# Teensylu-1_0.net
KiCad netlist of a schematic drawn in EAGLE
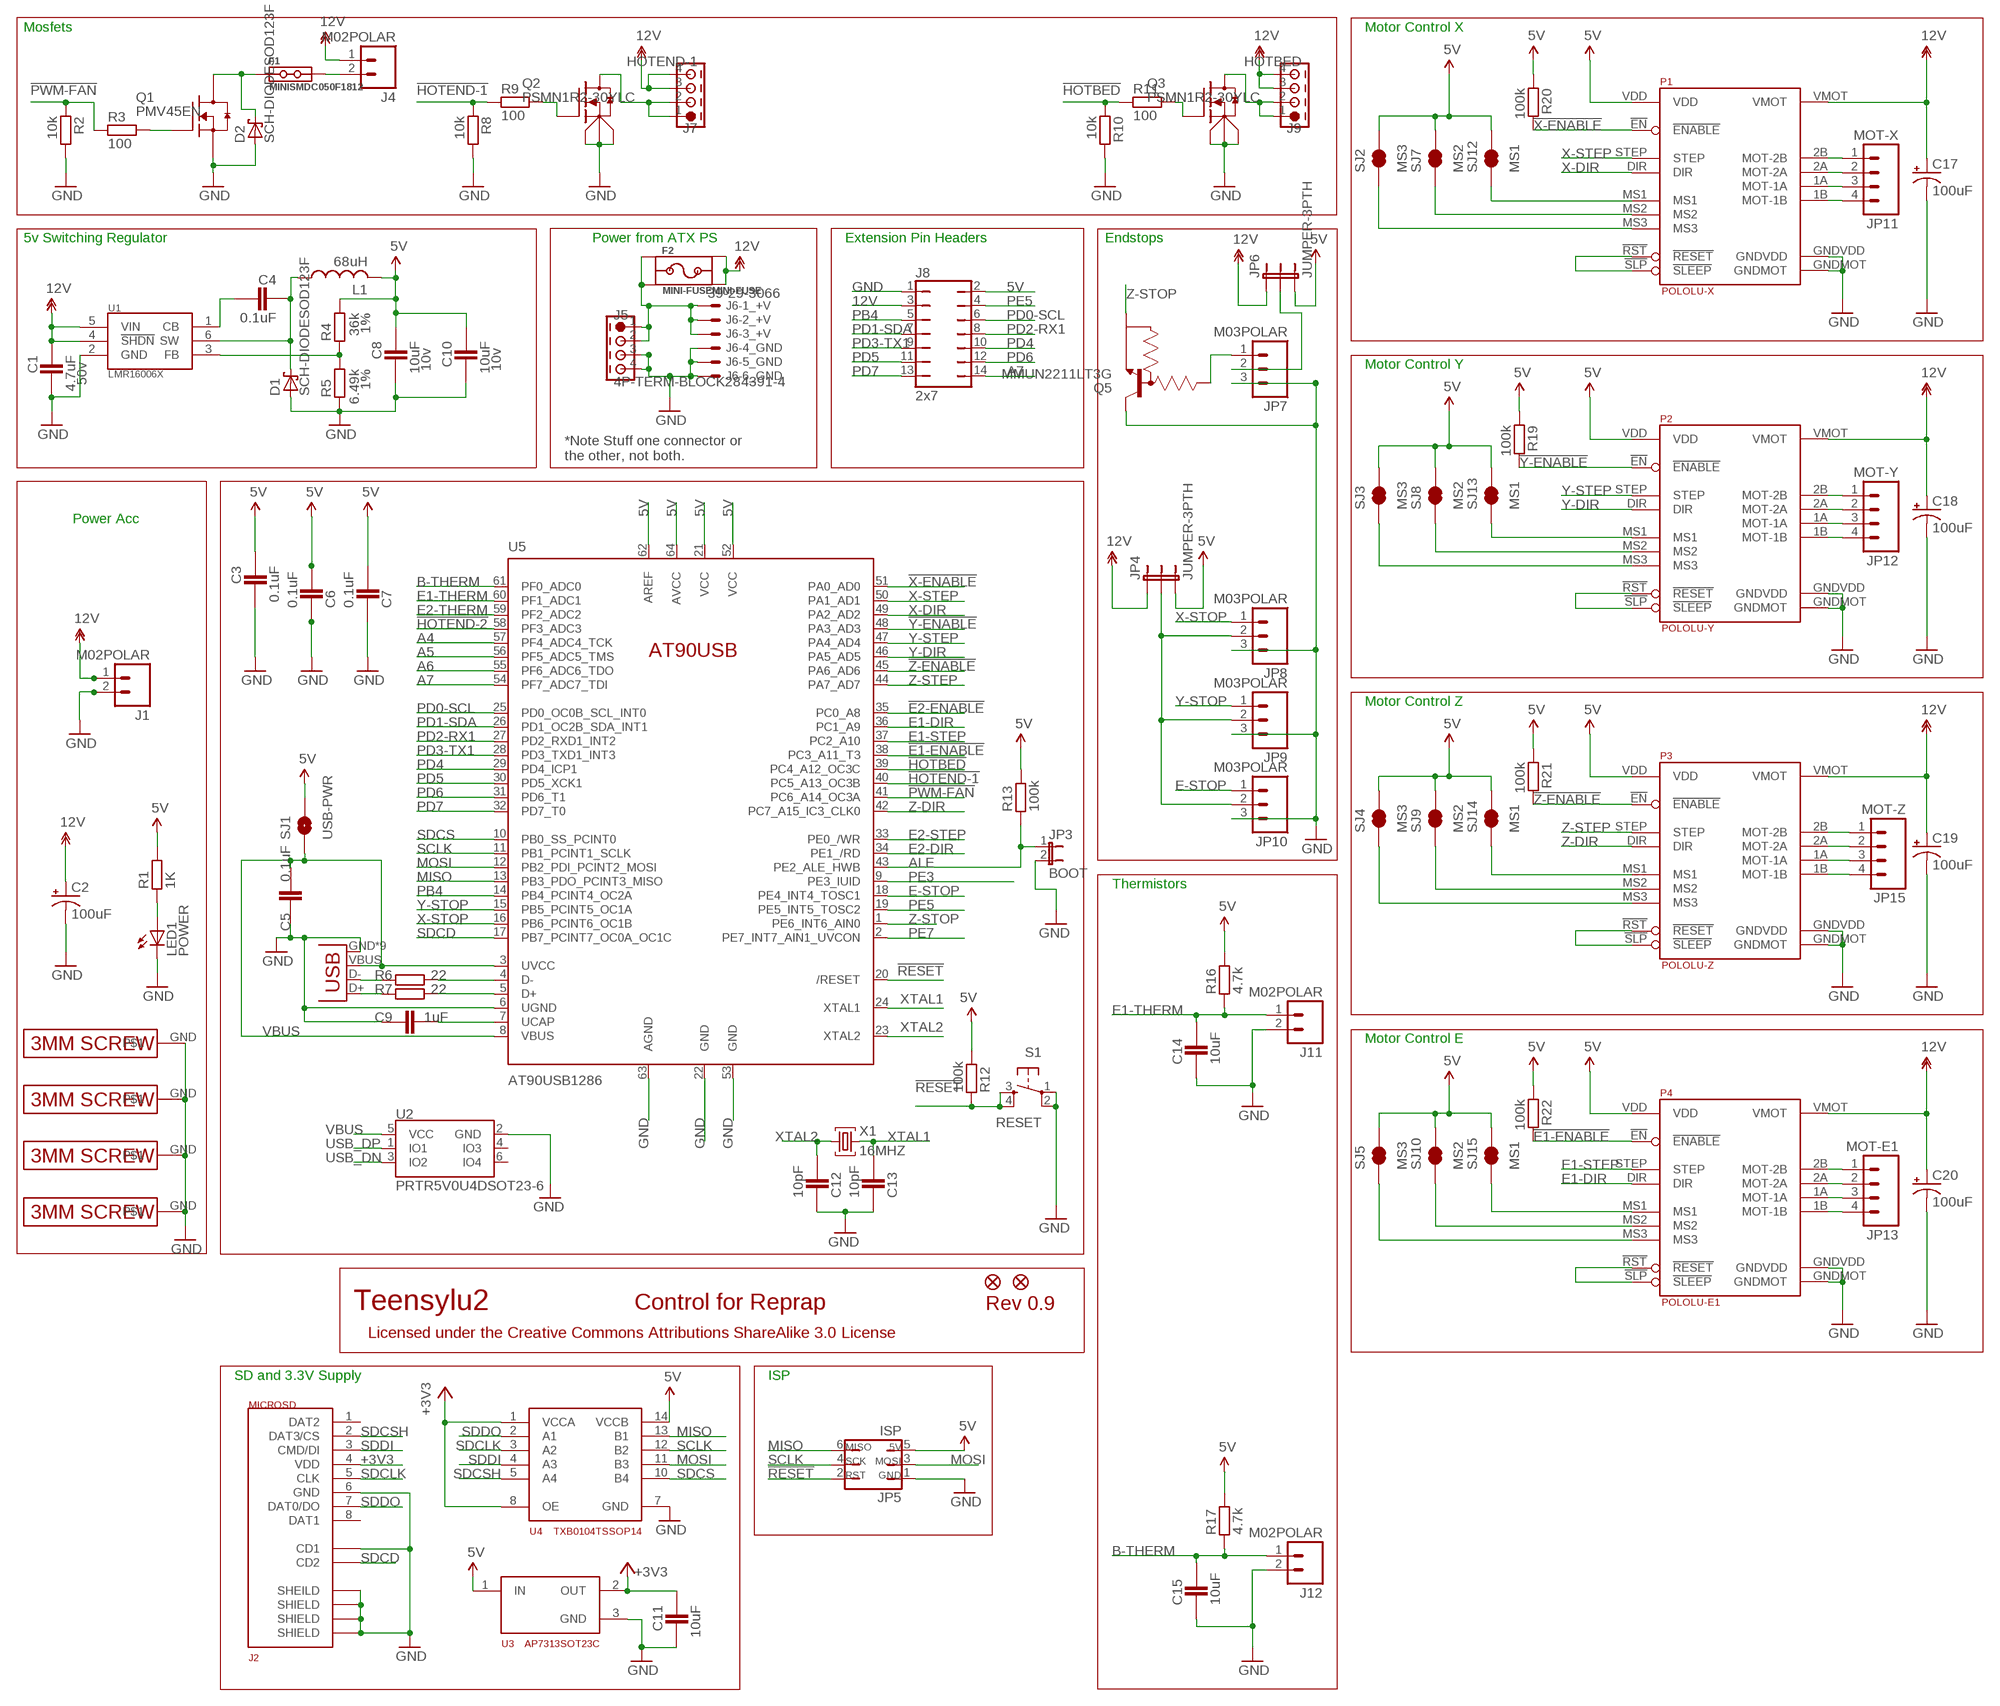
[diagram p0: schematic, sheet 1]

(export (version "E")
  (design (tool "Eeschema 10.0.6"))
  (components
    (comp (ref "C1")
      (value "4.7uF")
      (footprint "eagle-import:CAPC3215X168N")
      (fields
        (field (name "MANUFACTURER") "Yaiyo Yuden")
        (field (name "MANUFACTURER_PART_NUMBER") "UMK316AB7475KL-T")
        (field (name "TOLERANCE") "10%")
        (field (name "VDC") "50v")
      )
      (libsource (lib "eagle-import") (part "CAPACITOR_1206"))
    )
    (comp (ref "C2")
      (value "100uF")
      (footprint "eagle-import:PANASONIC_D")
      (fields
        (field (name "MANUFACTURER") "Panasonic")
        (field (name "MANUFACTURER_PART_NUMBER") "EEE-FTH101XAP")
        (field (name "TOLERANCE") "20%")
      )
      (libsource (lib "eagle-import") (part "CPOL-USD"))
    )
    (comp (ref "C3")
      (value "0.1uF")
      (footprint "eagle-import:CAPC1608X92N")
      (fields
        (field (name "MANUFACTURER") "Murata")
        (field (name "MANUFACTURER_PART_NUMBER") "GRM188R71C104KA01D")
        (field (name "TOLERANCE") "10%")
      )
      (libsource (lib "eagle-import") (part "CAPACITOR_0603"))
    )
    (comp (ref "C4")
      (value "0.1uF")
      (footprint "eagle-import:CAPC1608X92N")
      (fields
        (field (name "MANUFACTURER") "Samsung")
        (field (name "MANUFACTURER_PART_NUMBER") "CL10B104KB8NNNC")
        (field (name "TOLERANCE") "10%")
      )
      (libsource (lib "eagle-import") (part "CAPACITOR_0603"))
    )
    (comp (ref "C5")
      (value "0.1uF")
      (footprint "eagle-import:CAPC1608X92N")
      (fields
        (field (name "MANUFACTURER") "Murata")
        (field (name "MANUFACTURER_PART_NUMBER") "GRM188R71C104KA01D")
        (field (name "TOLERANCE") "10%")
      )
      (libsource (lib "eagle-import") (part "CAPACITOR_0603"))
    )
    (comp (ref "C6")
      (value "0.1uF")
      (footprint "eagle-import:CAPC1608X92N")
      (fields
        (field (name "MANUFACTURER") "Murata")
        (field (name "MANUFACTURER_PART_NUMBER") "GRM188R71C104KA01D")
        (field (name "TOLERANCE") "10%")
      )
      (libsource (lib "eagle-import") (part "CAPACITOR_0603"))
    )
    (comp (ref "C7")
      (value "0.1uF")
      (footprint "eagle-import:CAPC1608X92N")
      (fields
        (field (name "MANUFACTURER") "Murata")
        (field (name "MANUFACTURER_PART_NUMBER") "GRM188R71C104KA01D")
        (field (name "TOLERANCE") "10%")
      )
      (libsource (lib "eagle-import") (part "CAPACITOR_0603"))
    )
    (comp (ref "C8")
      (value "10uF")
      (footprint "eagle-import:CAPC2012X145AN")
      (fields
        (field (name "MANUFACTURER") "Murata")
        (field (name "MANUFACTURER_PART_NUMBER") "GRM21BR71A106KE51L")
        (field (name "TOLERANCE") "10%")
        (field (name "VDC") "10v")
      )
      (libsource (lib "eagle-import") (part "CAPACITOR_0805"))
    )
    (comp (ref "C9")
      (value "1uF")
      (footprint "eagle-import:CAPC1608X92N")
      (fields
        (field (name "MANUFACTURER") "Samsung")
        (field (name "MANUFACTURER_PART_NUMBER") "CL10A105MO8NNNC")
        (field (name "TOLERANCE") "20%")
      )
      (libsource (lib "eagle-import") (part "CAPACITOR_0603"))
    )
    (comp (ref "C10")
      (value "10uF")
      (footprint "eagle-import:CAPC2012X145AN")
      (fields
        (field (name "MANUFACTURER") "Murata")
        (field (name "MANUFACTURER_PART_NUMBER") "GRM21BR71A106KE51L")
        (field (name "TOLERANCE") "10%")
        (field (name "VDC") "10v")
      )
      (libsource (lib "eagle-import") (part "CAPACITOR_0805"))
    )
    (comp (ref "C11")
      (value "10uF")
      (footprint "eagle-import:CAPC1608X92N")
      (fields
        (field (name "MANUFACTURER") "Murata")
        (field (name "MANUFACTURER_PART_NUMBER") "GRM188R61C106MA73D")
        (field (name "TOLERANCE") "20%")
      )
      (libsource (lib "eagle-import") (part "CAPACITOR_0603"))
    )
    (comp (ref "C12")
      (value "10pF")
      (footprint "eagle-import:CAPC1608X92N")
      (fields
        (field (name "MANUFACTURER") "Samsung")
        (field (name "MANUFACTURER_PART_NUMBER") "CL10C100JB8NCNC")
        (field (name "TOLERANCE") "5%")
      )
      (libsource (lib "eagle-import") (part "CAPACITOR_0603"))
    )
    (comp (ref "C13")
      (value "10pF")
      (footprint "eagle-import:CAPC1608X92N")
      (fields
        (field (name "MANUFACTURER") "Samsung")
        (field (name "MANUFACTURER_PART_NUMBER") "CL10C100JB8NCNC")
        (field (name "TOLERANCE") "5%")
      )
      (libsource (lib "eagle-import") (part "CAPACITOR_0603"))
    )
    (comp (ref "C14")
      (value "10uF")
      (footprint "eagle-import:CAPC1608X92N")
      (fields
        (field (name "MANUFACTURER") "Murata")
        (field (name "MANUFACTURER_PART_NUMBER") "GRM188R61C106MA73D")
        (field (name "TOLERANCE") "20%")
      )
      (libsource (lib "eagle-import") (part "CAPACITOR_0603"))
    )
    (comp (ref "C15")
      (value "10uF")
      (footprint "eagle-import:CAPC1608X92N")
      (fields
        (field (name "MANUFACTURER") "Murata")
        (field (name "MANUFACTURER_PART_NUMBER") "GRM188R61C106MA73D")
        (field (name "TOLERANCE") "20%")
      )
      (libsource (lib "eagle-import") (part "CAPACITOR_0603"))
    )
    (comp (ref "C17")
      (value "100uF")
      (footprint "eagle-import:PANASONIC_D")
      (fields
        (field (name "MANUFACTURER") "Panasonic")
        (field (name "MANUFACTURER_PART_NUMBER") "EEE-FTH101XAP")
        (field (name "TOLERANCE") "20%")
      )
      (libsource (lib "eagle-import") (part "CPOL-USD"))
    )
    (comp (ref "C18")
      (value "100uF")
      (footprint "eagle-import:PANASONIC_D")
      (fields
        (field (name "MANUFACTURER") "Panasonic")
        (field (name "MANUFACTURER_PART_NUMBER") "EEE-FTH101XAP")
        (field (name "TOLERANCE") "20%")
      )
      (libsource (lib "eagle-import") (part "CPOL-USD"))
    )
    (comp (ref "C19")
      (value "100uF")
      (footprint "eagle-import:PANASONIC_D")
      (fields
        (field (name "MANUFACTURER") "Panasonic")
        (field (name "MANUFACTURER_PART_NUMBER") "EEE-FTH101XAP")
        (field (name "TOLERANCE") "20%")
      )
      (libsource (lib "eagle-import") (part "CPOL-USD"))
    )
    (comp (ref "C20")
      (value "100uF")
      (footprint "eagle-import:PANASONIC_D")
      (fields
        (field (name "MANUFACTURER") "Panasonic")
        (field (name "MANUFACTURER_PART_NUMBER") "EEE-FTH101XAP")
        (field (name "TOLERANCE") "20%")
      )
      (libsource (lib "eagle-import") (part "CPOL-USD"))
    )
    (comp (ref "D1")
      (value "SCH-DIODESOD123F")
      (footprint "eagle-import:SOD123F")
      (fields
        (field (name "MANUFACTURER") "NXP Semiconductors")
        (field (name "MANUFACTURER_PART_NUMBER") "PMEG4010CEH,115")
        (field (name "CURRENT") "1A")
        (field (name "MANUFACTURER_1") "NXP Semiconductors")
        (field (name "MANUFACTURER_PART_NUMBER_1") "PMEG4010CEH,115")
        (field (name "REVERSE_VOLTAGE") "40V")
      )
      (libsource (lib "eagle-import") (part "SCH-DIODESOD123F"))
    )
    (comp (ref "D2")
      (value "SCH-DIODESOD123F")
      (footprint "eagle-import:SOD123F")
      (fields
        (field (name "MANUFACTURER") "NXP Semiconductors")
        (field (name "MANUFACTURER_PART_NUMBER") "PMEG4010CEH,115")
        (field (name "CURRENT") "1A")
        (field (name "MANUFACTURER_1") "NXP Semiconductors")
      )
      (libsource (lib "eagle-import") (part "SCH-DIODESOD123F"))
    )
    (comp (ref "F1")
      (value "MINISMDC050F1812")
      (footprint "eagle-import:MINISMDC")
      (fields
        (field (name "MANUFACTURER") "TE Connectivity")
        (field (name "MANUFACTURER_PART_NUMBER") "MINISMDC050F-2")
      )
      (libsource (lib "eagle-import") (part "MINISMDC050F1812"))
    )
    (comp (ref "F2")
      (value "MINI-FUSEMINI-FUSE")
      (footprint "eagle-import:MINI_FUSE")
      (fields (field (name "MANUFACTURER") "Keystone") (field (name "MANUFACTURER_PART_NUMBER") "3568"))
      (libsource (lib "eagle-import") (part "MINI-FUSEMINI-FUSE"))
    )
    (comp (ref "J1")
      (value "M02POLAR")
      (footprint "eagle-import:MOLEX-1X2")
      (description "CONN HEADER 2POS .100 VERT TIN")
      (fields (field (name "MANUFACTURER") "Molex") (field (name "MANUFACTURER_PART_NUMBER") "0022272021"))
      (libsource (lib "eagle-import") (part "M02POLAR"))
    )
    (comp (ref "J2")
      (value "MICROSD")
      (footprint "eagle-import:AMPHENOL-MICROSD")
      (description "CONN MICRO SD CARD PUSH-PULL R/A")
      (fields
        (field (name "MANUFACTURER") "Amphenol")
        (field (name "MANUFACTURER_PART_NUMBER") "114-00841-68")
      )
      (libsource (lib "eagle-import") (part "MICROSD"))
    )
    (comp (ref "J3")
      (value "USB-MICRO-PTH")
      (footprint "eagle-import:USB-MICROB-PTH")
      (fields (field (name "MANUFACTURER") "FCI") (field (name "MANUFACTURER_PART_NUMBER") "10118194-0001LF"))
      (libsource (lib "eagle-import") (part "USB-MICRO-PTH"))
    )
    (comp (ref "J4")
      (value "M02POLAR")
      (footprint "eagle-import:MOLEX-1X2")
      (description "CONN HEADER 2POS .100 VERT TIN")
      (fields (field (name "MANUFACTURER") "Molex") (field (name "MANUFACTURER_PART_NUMBER") "0022272021"))
      (libsource (lib "eagle-import") (part "M02POLAR"))
    )
    (comp (ref "J5")
      (value "4P-TERM-BLOCK284391-4")
      (footprint "eagle-import:284391-4")
      (fields
        (field (name "MANUFACTURER") "TE Connectivity")
        (field (name "MANUFACTURER_PART_NUMBER") "284391-4")
      )
      (libsource (lib "eagle-import") (part "4P-TERM-BLOCK284391-4"))
    )
    (comp (ref "J6")
      (value "39-29-3066")
      (footprint "eagle-import:39-29-3066")
      (fields (field (name "MANUFACTURER") "Molex") (field (name "MANUFACTURER_PART_NUMBER") "0039293066"))
      (libsource (lib "eagle-import") (part "39-29-3066"))
    )
    (comp (ref "J7")
      (value "HOTEND-1")
      (footprint "eagle-import:284391-4")
      (fields
        (field (name "MANUFACTURER") "TE Connectivity")
        (field (name "MANUFACTURER_PART_NUMBER") "284391-4")
      )
      (libsource (lib "eagle-import") (part "4P-TERM-BLOCK284391-4"))
    )
    (comp (ref "J8")
      (value "2x7")
      (footprint "eagle-import:JP7Q")
      (description "DIL VERTICAL PC TAIL PIN HEADER")
      (fields (field (name "MANUFACTURER") "Harwin") (field (name "MANUFACTURER_PART_NUMBER") "M20-9980746"))
      (libsource (lib "eagle-import") (part "JP7Q"))
    )
    (comp (ref "J9")
      (value "HOTBED")
      (footprint "eagle-import:284391-4")
      (fields
        (field (name "MANUFACTURER") "TE Connectivity")
        (field (name "MANUFACTURER_PART_NUMBER") "284391-4")
      )
      (libsource (lib "eagle-import") (part "4P-TERM-BLOCK284391-4"))
    )
    (comp (ref "J11")
      (value "M02POLAR")
      (footprint "eagle-import:MOLEX-1X2")
      (description "CONN HEADER 2POS .100 VERT TIN")
      (fields (field (name "MANUFACTURER") "Molex") (field (name "MANUFACTURER_PART_NUMBER") "0022272021"))
      (libsource (lib "eagle-import") (part "M02POLAR"))
    )
    (comp (ref "J12")
      (value "M02POLAR")
      (footprint "eagle-import:MOLEX-1X2")
      (description "CONN HEADER 2POS .100 VERT TIN")
      (fields (field (name "MANUFACTURER") "Molex") (field (name "MANUFACTURER_PART_NUMBER") "0022272021"))
      (libsource (lib "eagle-import") (part "M02POLAR"))
    )
    (comp (ref "JP1")
      (value "FIDUCIAL1X2.5")
      (footprint "eagle-import:FIDUCIAL-1X2.5")
      (libsource (lib "eagle-import") (part "FIDUCIAL1X2.5"))
    )
    (comp (ref "JP2")
      (value "FIDUCIAL1X2.5")
      (footprint "eagle-import:FIDUCIAL-1X2.5")
      (libsource (lib "eagle-import") (part "FIDUCIAL1X2.5"))
    )
    (comp (ref "JP3")
      (value "BOOT")
      (footprint "eagle-import:1X02")
      (description "SIL VERTICAL PC TAIL PIN HEADER")
      (fields (field (name "MANUFACTURER") "Harwin") (field (name "MANUFACTURER_PART_NUMBER") "M20-9990246"))
      (libsource (lib "eagle-import") (part "JUMPER-2PTH"))
    )
    (comp (ref "JP4")
      (value "JUMPER-3PTH")
      (footprint "eagle-import:1X03")
      (libsource (lib "eagle-import") (part "JUMPER-3PTH"))
    )
    (comp (ref "JP5")
      (value "ISP")
      (footprint "eagle-import:ISP")
      (libsource (lib "eagle-import") (part "PROGHEADER"))
    )
    (comp (ref "JP6")
      (value "JUMPER-3PTH")
      (footprint "eagle-import:1X03")
      (libsource (lib "eagle-import") (part "JUMPER-3PTH"))
    )
    (comp (ref "JP7")
      (value "M03POLAR")
      (footprint "eagle-import:MOLEX-1X3")
      (description "CONN HEADER 3POS .100 VERT TIN")
      (fields (field (name "MANUFACTURER") "Molex") (field (name "MANUFACTURER_PART_NUMBER") "0022272031"))
      (libsource (lib "eagle-import") (part "M03POLAR"))
    )
    (comp (ref "JP8")
      (value "M03POLAR")
      (footprint "eagle-import:MOLEX-1X3")
      (description "CONN HEADER 3POS .100 VERT TIN")
      (fields (field (name "MANUFACTURER") "Molex") (field (name "MANUFACTURER_PART_NUMBER") "0022272031"))
      (libsource (lib "eagle-import") (part "M03POLAR"))
    )
    (comp (ref "JP9")
      (value "M03POLAR")
      (footprint "eagle-import:MOLEX-1X3")
      (description "CONN HEADER 3POS .100 VERT TIN")
      (fields (field (name "MANUFACTURER") "Molex") (field (name "MANUFACTURER_PART_NUMBER") "0022272031"))
      (libsource (lib "eagle-import") (part "M03POLAR"))
    )
    (comp (ref "JP10")
      (value "M03POLAR")
      (footprint "eagle-import:MOLEX-1X3")
      (description "CONN HEADER 3POS .100 VERT TIN")
      (fields (field (name "MANUFACTURER") "Molex") (field (name "MANUFACTURER_PART_NUMBER") "0022272031"))
      (libsource (lib "eagle-import") (part "M03POLAR"))
    )
    (comp (ref "JP11")
      (value "MOT-X")
      (footprint "eagle-import:MOLEX-1X4")
      (fields (field (name "MANUFACTURER") "Molex") (field (name "MANUFACTURER_PART_NUMBER") "0022272041"))
      (libsource (lib "eagle-import") (part "M04POLAR"))
    )
    (comp (ref "JP12")
      (value "MOT-Y")
      (footprint "eagle-import:MOLEX-1X4")
      (fields (field (name "MANUFACTURER") "Molex") (field (name "MANUFACTURER_PART_NUMBER") "0022272041"))
      (libsource (lib "eagle-import") (part "M04POLAR"))
    )
    (comp (ref "JP13")
      (value "MOT-E1")
      (footprint "eagle-import:MOLEX-1X4")
      (fields (field (name "MANUFACTURER") "Molex") (field (name "MANUFACTURER_PART_NUMBER") "0022272041"))
      (libsource (lib "eagle-import") (part "M04POLAR"))
    )
    (comp (ref "JP15")
      (value "MOT-Z")
      (footprint "eagle-import:MOLEX-1X4")
      (fields (field (name "MANUFACTURER") "Molex") (field (name "MANUFACTURER_PART_NUMBER") "0022272041"))
      (libsource (lib "eagle-import") (part "M04POLAR"))
    )
    (comp (ref "L1")
      (value "68uH")
      (footprint "eagle-import:SRN6045")
      (fields
        (field (name "MANUFACTURER") "Bourns")
        (field (name "MANUFACTURER_PART_NUMBER") "SRN6045-680M")
        (field (name "MANUFACTURER_1") "Bourns")
        (field (name "MANUFACTURER_PART_NUMBER_1") "SRN6045-680M")
      )
      (libsource (lib "eagle-import") (part "INDUCTORSRN6045"))
    )
    (comp (ref "LED1")
      (value "POWER")
      (footprint "eagle-import:CHIPLED_0805")
      (fields
        (field (name "MANUFACTURER") "Kingbright")
        (field (name "MANUFACTURER_PART_NUMBER") "APT2012SGC")
      )
      (libsource (lib "eagle-import") (part "LEDCHIPLED_0805"))
    )
    (comp (ref "P1")
      (value "POLOLU-X")
      (footprint "eagle-import:POLOLU-STEPPER-PTH")
      (libsource (lib "eagle-import") (part "POLOLU-ALLEGRO"))
    )
    (comp (ref "P2")
      (value "POLOLU-Y")
      (footprint "eagle-import:POLOLU-STEPPER-PTH")
      (libsource (lib "eagle-import") (part "POLOLU-ALLEGRO"))
    )
    (comp (ref "P3")
      (value "POLOLU-Z")
      (footprint "eagle-import:POLOLU-STEPPER-PTH")
      (libsource (lib "eagle-import") (part "POLOLU-ALLEGRO"))
    )
    (comp (ref "P4")
      (value "POLOLU-E1")
      (footprint "eagle-import:POLOLU-STEPPER-PTH")
      (libsource (lib "eagle-import") (part "POLOLU-ALLEGRO"))
    )
    (comp (ref "Q1")
      (value "PMV45EN")
      (footprint "eagle-import:SOT23C")
      (fields
        (field (name "MANUFACTURER") "International Rectifier")
        (field (name "MANUFACTURER_PART_NUMBER") "IRLML2060TRPBF")
        (field (name "VOLTAGE") "60V")
      )
      (libsource (lib "eagle-import") (part "MOSFET-NCH_SOT-23"))
    )
    (comp (ref "Q2")
      (value "PSMN1R2-30YLC")
      (footprint "eagle-import:LFPACK-POWERPAK-SO8")
      (fields
        (field (name "MANUFACTURER") "NXP Semiconductors")
        (field (name "MANUFACTURER_PART_NUMBER") "PSMN1R2-30YLC,115")
        (field (name "VOLTAGE") "30V")
      )
      (libsource (lib "eagle-import") (part "PSMN1R2-30YLCPOWERPACK-S08"))
    )
    (comp (ref "Q3")
      (value "PSMN1R2-30YLC")
      (footprint "eagle-import:LFPACK-POWERPAK-SO8")
      (fields
        (field (name "MANUFACTURER") "NXP Semiconductors")
        (field (name "MANUFACTURER_PART_NUMBER") "PSMN1R2-30YLC,115")
        (field (name "VOLTAGE") "30V")
      )
      (libsource (lib "eagle-import") (part "PSMN1R2-30YLCPOWERPACK-S08"))
    )
    (comp (ref "Q5")
      (value "MMUN2211LT3G")
      (footprint "eagle-import:SOT23C")
      (description "TRANS PREBIAS NPN 246MW SOT23-3")
      (fields (field (name "MANUFACTURER") "ON Semiconductor"))
      (libsource (lib "eagle-import") (part "TRANSISTOR_NPN_BIASSOT23C"))
    )
    (comp (ref "R1")
      (value "1K")
      (footprint "eagle-import:RESC1608X55N")
      (libsource (lib "eagle-import") (part "RESISTOR_0603"))
    )
    (comp (ref "R2")
      (value "10k")
      (footprint "eagle-import:RESC1608X55N")
      (libsource (lib "eagle-import") (part "RESISTOR_0603"))
    )
    (comp (ref "R3")
      (value "100")
      (footprint "eagle-import:RESC1608X55N")
      (libsource (lib "eagle-import") (part "RESISTOR_0603"))
    )
    (comp (ref "R4")
      (value "36k")
      (footprint "eagle-import:RESC1608X55N")
      (fields (field (name "TOLERANCE") "1%"))
      (libsource (lib "eagle-import") (part "RESISTOR_0603"))
    )
    (comp (ref "R5")
      (value "6.49k")
      (footprint "eagle-import:RESC1608X55N")
      (fields (field (name "TOLERANCE") "1%"))
      (libsource (lib "eagle-import") (part "RESISTOR_0603"))
    )
    (comp (ref "R6")
      (value "22")
      (footprint "eagle-import:RESC1608X55N")
      (libsource (lib "eagle-import") (part "RESISTOR_0603"))
    )
    (comp (ref "R7")
      (value "22")
      (footprint "eagle-import:RESC1608X55N")
      (libsource (lib "eagle-import") (part "RESISTOR_0603"))
    )
    (comp (ref "R8")
      (value "10k")
      (footprint "eagle-import:RESC1608X55N")
      (libsource (lib "eagle-import") (part "RESISTOR_0603"))
    )
    (comp (ref "R9")
      (value "100")
      (footprint "eagle-import:RESC1608X55N")
      (libsource (lib "eagle-import") (part "RESISTOR_0603"))
    )
    (comp (ref "R10")
      (value "10k")
      (footprint "eagle-import:RESC1608X55N")
      (libsource (lib "eagle-import") (part "RESISTOR_0603"))
    )
    (comp (ref "R11")
      (value "100")
      (footprint "eagle-import:RESC1608X55N")
      (libsource (lib "eagle-import") (part "RESISTOR_0603"))
    )
    (comp (ref "R12")
      (value "100k")
      (footprint "eagle-import:RESC1608X55N")
      (libsource (lib "eagle-import") (part "RESISTOR_0603"))
    )
    (comp (ref "R13")
      (value "100k")
      (footprint "eagle-import:RESC1608X55N")
      (libsource (lib "eagle-import") (part "RESISTOR_0603"))
    )
    (comp (ref "R16")
      (value "4.7k")
      (footprint "eagle-import:RESC1608X55N")
      (libsource (lib "eagle-import") (part "RESISTOR_0603"))
    )
    (comp (ref "R17")
      (value "4.7k")
      (footprint "eagle-import:RESC1608X55N")
      (libsource (lib "eagle-import") (part "RESISTOR_0603"))
    )
    (comp (ref "R19")
      (value "100k")
      (footprint "eagle-import:RESC1608X55N")
      (libsource (lib "eagle-import") (part "RESISTOR_0603"))
    )
    (comp (ref "R20")
      (value "100k")
      (footprint "eagle-import:RESC1608X55N")
      (libsource (lib "eagle-import") (part "RESISTOR_0603"))
    )
    (comp (ref "R21")
      (value "100k")
      (footprint "eagle-import:RESC1608X55N")
      (libsource (lib "eagle-import") (part "RESISTOR_0603"))
    )
    (comp (ref "R22")
      (value "100k")
      (footprint "eagle-import:RESC1608X55N")
      (libsource (lib "eagle-import") (part "RESISTOR_0603"))
    )
    (comp (ref "S1")
      (value "RESET")
      (footprint "eagle-import:TACTILE_SWITCH_SMD")
      (fields (field (name "MANUFACTURER") "Bourns") (field (name "MANUFACTURER_PART_NUMBER") "7914J-1-000E"))
      (libsource (lib "eagle-import") (part "TAC_SWITCHSMD"))
    )
    (comp (ref "SCREW1")
      (value "3MM-SCREW")
      (footprint "eagle-import:PLATEDSCREW")
      (libsource (lib "eagle-import") (part "3MM-SCREW"))
    )
    (comp (ref "SCREW2")
      (value "3MM-SCREW")
      (footprint "eagle-import:PLATEDSCREW")
      (libsource (lib "eagle-import") (part "3MM-SCREW"))
    )
    (comp (ref "SCREW3")
      (value "3MM-SCREW")
      (footprint "eagle-import:PLATEDSCREW")
      (libsource (lib "eagle-import") (part "3MM-SCREW"))
    )
    (comp (ref "SCREW4")
      (value "3MM-SCREW")
      (footprint "eagle-import:PLATEDSCREW")
      (libsource (lib "eagle-import") (part "3MM-SCREW"))
    )
    (comp (ref "SJ1")
      (value "USB-PWR")
      (footprint "eagle-import:SJ_2S-NO")
      (libsource (lib "eagle-import") (part "SOLDERJUMPERNO"))
    )
    (comp (ref "SJ2")
      (value "MS3")
      (footprint "eagle-import:SJ_2S-TRACE")
      (libsource (lib "eagle-import") (part "SOLDERJUMPER-NCSJ-TRACE"))
    )
    (comp (ref "SJ3")
      (value "MS3")
      (footprint "eagle-import:SJ_2S-TRACE")
      (libsource (lib "eagle-import") (part "SOLDERJUMPER-NCSJ-TRACE"))
    )
    (comp (ref "SJ4")
      (value "MS3")
      (footprint "eagle-import:SJ_2S-TRACE")
      (libsource (lib "eagle-import") (part "SOLDERJUMPER-NCSJ-TRACE"))
    )
    (comp (ref "SJ5")
      (value "MS3")
      (footprint "eagle-import:SJ_2S-TRACE")
      (libsource (lib "eagle-import") (part "SOLDERJUMPER-NCSJ-TRACE"))
    )
    (comp (ref "SJ7")
      (value "MS2")
      (footprint "eagle-import:SJ_2S-TRACE")
      (libsource (lib "eagle-import") (part "SOLDERJUMPER-NCSJ-TRACE"))
    )
    (comp (ref "SJ8")
      (value "MS2")
      (footprint "eagle-import:SJ_2S-TRACE")
      (libsource (lib "eagle-import") (part "SOLDERJUMPER-NCSJ-TRACE"))
    )
    (comp (ref "SJ9")
      (value "MS2")
      (footprint "eagle-import:SJ_2S-TRACE")
      (libsource (lib "eagle-import") (part "SOLDERJUMPER-NCSJ-TRACE"))
    )
    (comp (ref "SJ10")
      (value "MS2")
      (footprint "eagle-import:SJ_2S-TRACE")
      (libsource (lib "eagle-import") (part "SOLDERJUMPER-NCSJ-TRACE"))
    )
    (comp (ref "SJ12")
      (value "MS1")
      (footprint "eagle-import:SJ_2S-TRACE")
      (libsource (lib "eagle-import") (part "SOLDERJUMPER-NCSJ-TRACE"))
    )
    (comp (ref "SJ13")
      (value "MS1")
      (footprint "eagle-import:SJ_2S-TRACE")
      (libsource (lib "eagle-import") (part "SOLDERJUMPER-NCSJ-TRACE"))
    )
    (comp (ref "SJ14")
      (value "MS1")
      (footprint "eagle-import:SJ_2S-TRACE")
      (libsource (lib "eagle-import") (part "SOLDERJUMPER-NCSJ-TRACE"))
    )
    (comp (ref "SJ15")
      (value "MS1")
      (footprint "eagle-import:SJ_2S-TRACE")
      (libsource (lib "eagle-import") (part "SOLDERJUMPER-NCSJ-TRACE"))
    )
    (comp (ref "U1")
      (value "LMR16006X")
      (footprint "eagle-import:TSOT6")
      (fields
        (field (name "MANUFACTURER") "Texas Instruments")
        (field (name "MANUFACTURER_PART_NUMBER") "LMR16006XDDCT")
      )
      (libsource (lib "eagle-import") (part "LMR16006X"))
    )
    (comp (ref "U2")
      (value "PRTR5V0U4DSOT23-6")
      (footprint "eagle-import:SOT23-6")
      (fields
        (field (name "MANUFACTURER") "NXP Semiconductors")
        (field (name "MANUFACTURER_PART_NUMBER") "PRTR5V0U4D,125")
      )
      (libsource (lib "eagle-import") (part "PRTR5V0U4DSOT23-6"))
    )
    (comp (ref "U3")
      (value "AP7313SOT23C")
      (footprint "eagle-import:SOT23C")
      (description "IC REG LDO 3.3V 0.15A SOT23-3")
      (fields
        (field (name "MANUFACTURER") "Diodes Incorporated")
        (field (name "MANUFACTURER_PART_NUMBER") "AP7313-33SAG-7")
      )
      (libsource (lib "eagle-import") (part "AP7313SOT23C"))
    )
    (comp (ref "U4")
      (value "TXB0104TSSOP14")
      (footprint "eagle-import:TSSOP14")
      (description "IC VOLT-LEVEL TRANSLATOR 14TSSOP")
      (fields
        (field (name "MANUFACTURER") "Texas Instruments")
        (field (name "MANUFACTURER_PART_NUMBER") "TXB0104PWR")
      )
      (libsource (lib "eagle-import") (part "TXB0104TSSOP14"))
    )
    (comp (ref "U5")
      (value "AT90USB1286")
      (footprint "eagle-import:TQFP64-2")
      (fields (field (name "MANUFACTURER") "Atmel"))
      (libsource (lib "eagle-import") (part "AT90USB"))
    )
    (comp (ref "X1")
      (value "16MHZ")
      (footprint "eagle-import:NDK-XTAL")
      (fields
        (field (name "MANUFACTURER") "NDK")
        (field (name "MANUFACTURER_PART_NUMBER") "NX5032GA-16.000000MHZ-LN-CD-1")
      )
      (libsource (lib "eagle-import") (part "XTAL"))
    )
  )
  (nets
    (net (code "1") (name "+3V3") (class "Default")
      (node (ref "C11") (pin "1") (pinfunction "1_1") (pintype "passive"))
      (node (ref "J2") (pin "4") (pinfunction "VDD_4") (pintype "power_in"))
      (node (ref "U3") (pin "2") (pinfunction "OUT_2") (pintype "power_in"))
      (node (ref "U4") (pin "1") (pinfunction "VCCA_1") (pintype "power_in"))
      (node (ref "U4") (pin "8") (pinfunction "OE_8") (pintype "input"))
    )
    (net (code "2") (name "/A4") (class "Default")
      (node (ref "U5") (pin "57") (pinfunction "PF4_ADC4_TCK_57") (pintype "bidirectional"))
    )
    (net (code "3") (name "/A5") (class "Default")
      (node (ref "U5") (pin "56") (pinfunction "PF5_ADC5_TMS_56") (pintype "bidirectional"))
    )
    (net (code "4") (name "/A6") (class "Default")
      (node (ref "U5") (pin "55") (pinfunction "PF6_ADC6_TDO_55") (pintype "bidirectional"))
    )
    (net (code "5") (name "/A7") (class "Default")
      (node (ref "J8") (pin "14") (pinfunction "14_14") (pintype "passive"))
      (node (ref "U5") (pin "54") (pinfunction "PF7_ADC7_TDI_54") (pintype "bidirectional"))
    )
    (net (code "6") (name "/ALE") (class "Default")
      (node (ref "JP3") (pin "1") (pinfunction "1_1") (pintype "passive"))
      (node (ref "R13") (pin "1") (pinfunction "1_1") (pintype "passive"))
      (node (ref "U5") (pin "43") (pinfunction "PE2_ALE_HWB_43") (pintype "bidirectional"))
    )
    (net (code "7") (name "/B-THERM") (class "Default")
      (node (ref "C15") (pin "2") (pinfunction "2_2") (pintype "passive"))
      (node (ref "J12") (pin "1") (pinfunction "1_1") (pintype "passive"))
      (node (ref "R17") (pin "1") (pinfunction "1_1") (pintype "passive"))
      (node (ref "U5") (pin "61") (pinfunction "PF0_ADC0_61") (pintype "bidirectional"))
    )
    (net (code "8") (name "/E-STOP") (class "Default")
      (node (ref "JP10") (pin "1") (pinfunction "1_1") (pintype "passive"))
      (node (ref "U5") (pin "18") (pinfunction "PE4_INT4_TOSC1_18") (pintype "bidirectional"))
    )
    (net (code "9") (name "/E1-DIR") (class "Default")
      (node (ref "P4") (pin "DIR") (pinfunction "DIR_DIR") (pintype "bidirectional"))
      (node (ref "U5") (pin "36") (pinfunction "PC1_A9_36") (pintype "bidirectional"))
    )
    (net (code "10") (name "/E1-STEP") (class "Default")
      (node (ref "P4") (pin "STEP") (pinfunction "STEP_STEP") (pintype "bidirectional"))
      (node (ref "U5") (pin "37") (pinfunction "PC2_A10_37") (pintype "bidirectional"))
    )
    (net (code "11") (name "/E1-THERM") (class "Default")
      (node (ref "C14") (pin "2") (pinfunction "2_2") (pintype "passive"))
      (node (ref "J11") (pin "1") (pinfunction "1_1") (pintype "passive"))
      (node (ref "R16") (pin "1") (pinfunction "1_1") (pintype "passive"))
      (node (ref "U5") (pin "60") (pinfunction "PF1_ADC1_60") (pintype "bidirectional"))
    )
    (net (code "12") (name "/E2-DIR") (class "Default")
      (node (ref "U5") (pin "34") (pinfunction "PE1_/RD_34") (pintype "bidirectional"))
    )
    (net (code "13") (name "/E2-STEP") (class "Default")
      (node (ref "U5") (pin "33") (pinfunction "PE0_/WR_33") (pintype "bidirectional"))
    )
    (net (code "14") (name "/E2-THERM") (class "Default")
      (node (ref "U5") (pin "59") (pinfunction "PF2_ADC2_59") (pintype "bidirectional"))
    )
    (net (code "15") (name "/MISO") (class "Default")
      (node (ref "JP5") (pin "6") (pinfunction "6_6") (pintype "passive"))
      (node (ref "U4") (pin "13") (pinfunction "B1_13") (pintype "bidirectional"))
      (node (ref "U5") (pin "13") (pinfunction "PB3_PDO_PCINT3_MISO_13") (pintype "bidirectional"))
    )
    (net (code "16") (name "/MOSI") (class "Default")
      (node (ref "JP5") (pin "3") (pinfunction "3_3") (pintype "passive"))
      (node (ref "U4") (pin "11") (pinfunction "B3_11") (pintype "bidirectional"))
      (node (ref "U5") (pin "12") (pinfunction "PB2_PDI_PCINT2_MOSI_12") (pintype "bidirectional"))
    )
    (net (code "17") (name "/PB4") (class "Default")
      (node (ref "J8") (pin "5") (pinfunction "5_5") (pintype "passive"))
      (node (ref "U5") (pin "14") (pinfunction "PB4_PCINT4_OC2A_14") (pintype "bidirectional"))
    )
    (net (code "18") (name "/PD0-SCL") (class "Default")
      (node (ref "J8") (pin "6") (pinfunction "6_6") (pintype "passive"))
      (node (ref "U5") (pin "25") (pinfunction "PD0_OC0B_SCL_INT0_25") (pintype "bidirectional"))
    )
    (net (code "19") (name "/PD1-SDA") (class "Default")
      (node (ref "J8") (pin "7") (pinfunction "7_7") (pintype "passive"))
      (node (ref "U5") (pin "26") (pinfunction "PD1_OC2B_SDA_INT1_26") (pintype "bidirectional"))
    )
    (net (code "20") (name "/PD2-RX1") (class "Default")
      (node (ref "J8") (pin "8") (pinfunction "8_8") (pintype "passive"))
      (node (ref "U5") (pin "27") (pinfunction "PD2_RXD1_INT2_27") (pintype "bidirectional"))
    )
    (net (code "21") (name "/PD3-TX1") (class "Default")
      (node (ref "J8") (pin "9") (pinfunction "9_9") (pintype "passive"))
      (node (ref "U5") (pin "28") (pinfunction "PD3_TXD1_INT3_28") (pintype "bidirectional"))
    )
    (net (code "22") (name "/PD4") (class "Default")
      (node (ref "J8") (pin "10") (pinfunction "10_10") (pintype "passive"))
      (node (ref "U5") (pin "29") (pinfunction "PD4_ICP1_29") (pintype "bidirectional"))
    )
    (net (code "23") (name "/PD5") (class "Default")
      (node (ref "J8") (pin "11") (pinfunction "11_11") (pintype "passive"))
      (node (ref "U5") (pin "30") (pinfunction "PD5_XCK1_30") (pintype "bidirectional"))
    )
    (net (code "24") (name "/PD6") (class "Default")
      (node (ref "J8") (pin "12") (pinfunction "12_12") (pintype "passive"))
      (node (ref "U5") (pin "31") (pinfunction "PD6_T1_31") (pintype "bidirectional"))
    )
    (net (code "25") (name "/PD7") (class "Default")
      (node (ref "J8") (pin "13") (pinfunction "13_13") (pintype "passive"))
      (node (ref "U5") (pin "32") (pinfunction "PD7_T0_32") (pintype "bidirectional"))
    )
    (net (code "26") (name "/PE3") (class "Default")
      (node (ref "U5") (pin "9") (pinfunction "PE3_IUID_9") (pintype "bidirectional"))
    )
    (net (code "27") (name "/PE5") (class "Default")
      (node (ref "J8") (pin "4") (pinfunction "4_4") (pintype "passive"))
      (node (ref "U5") (pin "19") (pinfunction "PE5_INT5_TOSC2_19") (pintype "bidirectional"))
    )
    (net (code "28") (name "/PE7") (class "Default")
      (node (ref "U5") (pin "2") (pinfunction "PE7_INT7_AIN1_UVCON_2") (pintype "bidirectional"))
    )
    (net (code "29") (name "/SCLK") (class "Default")
      (node (ref "JP5") (pin "4") (pinfunction "4_4") (pintype "passive"))
      (node (ref "U4") (pin "12") (pinfunction "B2_12") (pintype "bidirectional"))
      (node (ref "U5") (pin "11") (pinfunction "PB1_PCINT1_SCLK_11") (pintype "bidirectional"))
    )
    (net (code "30") (name "/SDCD") (class "Default")
      (node (ref "J2") (pin "CD2") (pinfunction "CD2_CD2") (pintype "bidirectional"))
      (node (ref "U5") (pin "17") (pinfunction "PB7_PCINT7_OC0A_OC1C_17") (pintype "bidirectional"))
    )
    (net (code "31") (name "/SDCLK") (class "Default")
      (node (ref "J2") (pin "5") (pinfunction "CLK_5") (pintype "input"))
      (node (ref "U4") (pin "3") (pinfunction "A2_3") (pintype "bidirectional"))
    )
    (net (code "32") (name "/SDCS") (class "Default")
      (node (ref "U4") (pin "10") (pinfunction "B4_10") (pintype "bidirectional"))
      (node (ref "U5") (pin "10") (pinfunction "PB0_SS_PCINT0_10") (pintype "bidirectional"))
    )
    (net (code "33") (name "/SDCSH") (class "Default")
      (node (ref "J2") (pin "2") (pinfunction "DAT3/CS_2") (pintype "bidirectional"))
      (node (ref "U4") (pin "5") (pinfunction "A4_5") (pintype "bidirectional"))
    )
    (net (code "34") (name "/SDDI") (class "Default")
      (node (ref "J2") (pin "3") (pinfunction "CMD/DI_3") (pintype "input"))
      (node (ref "U4") (pin "4") (pinfunction "A3_4") (pintype "bidirectional"))
    )
    (net (code "35") (name "/SDDO") (class "Default")
      (node (ref "J2") (pin "7") (pinfunction "DAT0/DO_7") (pintype "bidirectional"))
      (node (ref "U4") (pin "2") (pinfunction "A1_2") (pintype "bidirectional"))
    )
    (net (code "36") (name "/USB_DN") (class "Default")
      (node (ref "J3") (pin "D-") (pinfunction "D-_D-") (pintype "bidirectional"))
      (node (ref "R6") (pin "1") (pinfunction "1_1") (pintype "passive"))
      (node (ref "U2") (pin "3") (pinfunction "IO2_3") (pintype "bidirectional"))
    )
    (net (code "37") (name "/USB_DP") (class "Default")
      (node (ref "J3") (pin "D+") (pinfunction "D+_D+") (pintype "bidirectional"))
      (node (ref "R7") (pin "1") (pinfunction "1_1") (pintype "passive"))
      (node (ref "U2") (pin "1") (pinfunction "IO1_1") (pintype "bidirectional"))
    )
    (net (code "38") (name "/VBUS") (class "Default")
      (node (ref "C5") (pin "2") (pinfunction "2_2") (pintype "passive"))
      (node (ref "J3") (pin "VBUS") (pinfunction "VBUS_VBUS") (pintype "bidirectional"))
      (node (ref "SJ1") (pin "1") (pinfunction "1_1") (pintype "passive"))
      (node (ref "U2") (pin "5") (pinfunction "VCC_5") (pintype "power_in"))
      (node (ref "U5") (pin "3") (pinfunction "UVCC_3") (pintype "power_in"))
      (node (ref "U5") (pin "8") (pinfunction "VBUS_8") (pintype "bidirectional"))
    )
    (net (code "39") (name "/X-DIR") (class "Default")
      (node (ref "P1") (pin "DIR") (pinfunction "DIR_DIR") (pintype "bidirectional"))
      (node (ref "U5") (pin "49") (pinfunction "PA2_AD2_49") (pintype "bidirectional"))
    )
    (net (code "40") (name "/X-STEP") (class "Default")
      (node (ref "P1") (pin "STEP") (pinfunction "STEP_STEP") (pintype "bidirectional"))
      (node (ref "U5") (pin "50") (pinfunction "PA1_AD1_50") (pintype "bidirectional"))
    )
    (net (code "41") (name "/X-STOP") (class "Default")
      (node (ref "JP8") (pin "1") (pinfunction "1_1") (pintype "passive"))
      (node (ref "U5") (pin "16") (pinfunction "PB6_PCINT6_OC1B_16") (pintype "bidirectional"))
    )
    (net (code "42") (name "/XTAL1") (class "Default")
      (node (ref "C13") (pin "2") (pinfunction "2_2") (pintype "passive"))
      (node (ref "U5") (pin "24") (pinfunction "XTAL1_24") (pintype "passive"))
      (node (ref "X1") (pin "P$2") (pinfunction "2_P$2") (pintype "passive"))
    )
    (net (code "43") (name "/XTAL2") (class "Default")
      (node (ref "C12") (pin "2") (pinfunction "2_2") (pintype "passive"))
      (node (ref "U5") (pin "23") (pinfunction "XTAL2_23") (pintype "passive"))
      (node (ref "X1") (pin "P$1") (pinfunction "1_P$1") (pintype "passive"))
    )
    (net (code "44") (name "/Y-DIR") (class "Default")
      (node (ref "P2") (pin "DIR") (pinfunction "DIR_DIR") (pintype "bidirectional"))
      (node (ref "U5") (pin "46") (pinfunction "PA5_AD5_46") (pintype "bidirectional"))
    )
    (net (code "45") (name "/Y-STEP") (class "Default")
      (node (ref "P2") (pin "STEP") (pinfunction "STEP_STEP") (pintype "bidirectional"))
      (node (ref "U5") (pin "47") (pinfunction "PA4_AD4_47") (pintype "bidirectional"))
    )
    (net (code "46") (name "/Y-STOP") (class "Default")
      (node (ref "JP9") (pin "1") (pinfunction "1_1") (pintype "passive"))
      (node (ref "U5") (pin "15") (pinfunction "PB5_PCINT5_OC1A_15") (pintype "bidirectional"))
    )
    (net (code "47") (name "/Z-DIR") (class "Default")
      (node (ref "P3") (pin "DIR") (pinfunction "DIR_DIR") (pintype "bidirectional"))
      (node (ref "U5") (pin "42") (pinfunction "PC7_A15_IC3_CLK0_42") (pintype "bidirectional"))
    )
    (net (code "48") (name "/Z-STEP") (class "Default")
      (node (ref "P3") (pin "STEP") (pinfunction "STEP_STEP") (pintype "bidirectional"))
      (node (ref "U5") (pin "44") (pinfunction "PA7_AD7_44") (pintype "bidirectional"))
    )
    (net (code "49") (name "/Z-STOP") (class "Default")
      (node (ref "Q5") (pin "2") (pinfunction "E_2") (pintype "passive"))
      (node (ref "U5") (pin "1") (pinfunction "PE6_INT6_AIN0_1") (pintype "bidirectional"))
    )
    (net (code "50") (name "/~{E1-ENABLE}") (class "Default")
      (node (ref "P4") (pin "!EN") (pinfunction "~{ENABLE}_!EN") (pintype "input"))
      (node (ref "R22") (pin "2") (pinfunction "2_2") (pintype "passive"))
      (node (ref "U5") (pin "38") (pinfunction "PC3_A11_T3_38") (pintype "bidirectional"))
    )
    (net (code "51") (name "/~{E2-ENABLE}") (class "Default")
      (node (ref "U5") (pin "35") (pinfunction "PC0_A8_35") (pintype "bidirectional"))
    )
    (net (code "52") (name "/~{HOTBED}") (class "Default")
      (node (ref "R10") (pin "1") (pinfunction "1_1") (pintype "passive"))
      (node (ref "R11") (pin "1") (pinfunction "1_1") (pintype "passive"))
      (node (ref "U5") (pin "39") (pinfunction "PC4_A12_OC3C_39") (pintype "bidirectional"))
    )
    (net (code "53") (name "/~{HOTEND-1}") (class "Default")
      (node (ref "R8") (pin "1") (pinfunction "1_1") (pintype "passive"))
      (node (ref "R9") (pin "1") (pinfunction "1_1") (pintype "passive"))
      (node (ref "U5") (pin "40") (pinfunction "PC5_A13_OC3B_40") (pintype "bidirectional"))
    )
    (net (code "54") (name "/~{HOTEND-2}") (class "Default")
      (node (ref "U5") (pin "58") (pinfunction "PF3_ADC3_58") (pintype "bidirectional"))
    )
    (net (code "55") (name "/~{PWM-FAN}") (class "Default")
      (node (ref "R2") (pin "1") (pinfunction "1_1") (pintype "passive"))
      (node (ref "R3") (pin "1") (pinfunction "1_1") (pintype "passive"))
      (node (ref "U5") (pin "41") (pinfunction "PC6_A14_OC3A_41") (pintype "bidirectional"))
    )
    (net (code "56") (name "/~{RESET}") (class "Default")
      (node (ref "JP5") (pin "2") (pinfunction "2_2") (pintype "passive"))
      (node (ref "R12") (pin "1") (pinfunction "1_1") (pintype "passive"))
      (node (ref "S1") (pin "3") (pinfunction "3_3") (pintype "passive"))
      (node (ref "S1") (pin "4") (pinfunction "4_4") (pintype "passive"))
      (node (ref "U5") (pin "20") (pinfunction "/RESET_20") (pintype "bidirectional"))
    )
    (net (code "57") (name "/~{X-ENABLE}") (class "Default")
      (node (ref "P1") (pin "!EN") (pinfunction "~{ENABLE}_!EN") (pintype "input"))
      (node (ref "R20") (pin "2") (pinfunction "2_2") (pintype "passive"))
      (node (ref "U5") (pin "51") (pinfunction "PA0_AD0_51") (pintype "bidirectional"))
    )
    (net (code "58") (name "/~{Y-ENABLE}") (class "Default")
      (node (ref "P2") (pin "!EN") (pinfunction "~{ENABLE}_!EN") (pintype "input"))
      (node (ref "R19") (pin "2") (pinfunction "2_2") (pintype "passive"))
      (node (ref "U5") (pin "48") (pinfunction "PA3_AD3_48") (pintype "bidirectional"))
    )
    (net (code "59") (name "/~{Z-ENABLE}") (class "Default")
      (node (ref "P3") (pin "!EN") (pinfunction "~{ENABLE}_!EN") (pintype "input"))
      (node (ref "R21") (pin "2") (pinfunction "2_2") (pintype "passive"))
      (node (ref "U5") (pin "45") (pinfunction "PA6_AD6_45") (pintype "bidirectional"))
    )
    (net (code "60") (name "5V") (class "Default")
      (node (ref "C10") (pin "1") (pinfunction "1_1") (pintype "passive"))
      (node (ref "C3") (pin "1") (pinfunction "1_1") (pintype "passive"))
      (node (ref "C6") (pin "2") (pinfunction "2_2") (pintype "passive"))
      (node (ref "C7") (pin "2") (pinfunction "2_2") (pintype "passive"))
      (node (ref "C8") (pin "1") (pinfunction "1_1") (pintype "passive"))
      (node (ref "J8") (pin "2") (pinfunction "2_2") (pintype "passive"))
      (node (ref "JP4") (pin "3") (pinfunction "3_3") (pintype "passive"))
      (node (ref "JP5") (pin "5") (pinfunction "5_5") (pintype "passive"))
      (node (ref "JP6") (pin "3") (pinfunction "3_3") (pintype "passive"))
      (node (ref "L1") (pin "2") (pinfunction "2_2") (pintype "passive"))
      (node (ref "P1") (pin "VDD") (pinfunction "VDD_VDD") (pintype "power_in"))
      (node (ref "P2") (pin "VDD") (pinfunction "VDD_VDD") (pintype "power_in"))
      (node (ref "P3") (pin "VDD") (pinfunction "VDD_VDD") (pintype "power_in"))
      (node (ref "P4") (pin "VDD") (pinfunction "VDD_VDD") (pintype "power_in"))
      (node (ref "R1") (pin "2") (pinfunction "2_2") (pintype "passive"))
      (node (ref "R12") (pin "2") (pinfunction "2_2") (pintype "passive"))
      (node (ref "R13") (pin "2") (pinfunction "2_2") (pintype "passive"))
      (node (ref "R16") (pin "2") (pinfunction "2_2") (pintype "passive"))
      (node (ref "R17") (pin "2") (pinfunction "2_2") (pintype "passive"))
      (node (ref "R19") (pin "1") (pinfunction "1_1") (pintype "passive"))
      (node (ref "R20") (pin "1") (pinfunction "1_1") (pintype "passive"))
      (node (ref "R21") (pin "1") (pinfunction "1_1") (pintype "passive"))
      (node (ref "R22") (pin "1") (pinfunction "1_1") (pintype "passive"))
      (node (ref "R4") (pin "1") (pinfunction "1_1") (pintype "passive"))
      (node (ref "SJ1") (pin "2") (pinfunction "2_2") (pintype "passive"))
      (node (ref "SJ10") (pin "2") (pinfunction "2_2") (pintype "passive"))
      (node (ref "SJ12") (pin "2") (pinfunction "2_2") (pintype "passive"))
      (node (ref "SJ13") (pin "2") (pinfunction "2_2") (pintype "passive"))
      (node (ref "SJ14") (pin "2") (pinfunction "2_2") (pintype "passive"))
      (node (ref "SJ15") (pin "2") (pinfunction "2_2") (pintype "passive"))
      (node (ref "SJ2") (pin "2") (pinfunction "2_2") (pintype "passive"))
      (node (ref "SJ3") (pin "2") (pinfunction "2_2") (pintype "passive"))
      (node (ref "SJ4") (pin "2") (pinfunction "2_2") (pintype "passive"))
      (node (ref "SJ5") (pin "2") (pinfunction "2_2") (pintype "passive"))
      (node (ref "SJ7") (pin "2") (pinfunction "2_2") (pintype "passive"))
      (node (ref "SJ8") (pin "2") (pinfunction "2_2") (pintype "passive"))
      (node (ref "SJ9") (pin "2") (pinfunction "2_2") (pintype "passive"))
      (node (ref "U3") (pin "1") (pinfunction "IN_1") (pintype "power_in"))
      (node (ref "U4") (pin "14") (pinfunction "VCCB_14") (pintype "power_in"))
      (node (ref "U5") (pin "21") (pinfunction "VCC_21") (pintype "power_in"))
      (node (ref "U5") (pin "52") (pinfunction "VCC_52") (pintype "power_in"))
      (node (ref "U5") (pin "62") (pinfunction "AREF_62") (pintype "power_in"))
      (node (ref "U5") (pin "64") (pinfunction "AVCC_64") (pintype "power_in"))
    )
    (net (code "61") (name "12V") (class "Default")
      (node (ref "C1") (pin "1") (pinfunction "1_1") (pintype "passive"))
      (node (ref "C17") (pin "+") (pinfunction "+_+") (pintype "passive"))
      (node (ref "C18") (pin "+") (pinfunction "+_+") (pintype "passive"))
      (node (ref "C19") (pin "+") (pinfunction "+_+") (pintype "passive"))
      (node (ref "C2") (pin "+") (pinfunction "+_+") (pintype "passive"))
      (node (ref "C20") (pin "+") (pinfunction "+_+") (pintype "passive"))
      (node (ref "F2") (pin "P$3") (pinfunction "P$3_P$3") (pintype "passive"))
      (node (ref "F2") (pin "P$4") (pinfunction "P$4_P$4") (pintype "passive"))
      (node (ref "J1") (pin "1") (pinfunction "1_1") (pintype "passive"))
      (node (ref "J4") (pin "1") (pinfunction "1_1") (pintype "passive"))
      (node (ref "J7") (pin "3") (pinfunction "3_3") (pintype "power_in"))
      (node (ref "J7") (pin "4") (pinfunction "4_4") (pintype "power_in"))
      (node (ref "J8") (pin "3") (pinfunction "3_3") (pintype "passive"))
      (node (ref "J9") (pin "3") (pinfunction "3_3") (pintype "power_in"))
      (node (ref "J9") (pin "4") (pinfunction "4_4") (pintype "power_in"))
      (node (ref "JP4") (pin "1") (pinfunction "1_1") (pintype "passive"))
      (node (ref "JP6") (pin "1") (pinfunction "1_1") (pintype "passive"))
      (node (ref "P1") (pin "VMOT") (pinfunction "VMOT_VMOT") (pintype "power_in"))
      (node (ref "P2") (pin "VMOT") (pinfunction "VMOT_VMOT") (pintype "power_in"))
      (node (ref "P3") (pin "VMOT") (pinfunction "VMOT_VMOT") (pintype "power_in"))
      (node (ref "P4") (pin "VMOT") (pinfunction "VMOT_VMOT") (pintype "power_in"))
      (node (ref "U1") (pin "4") (pinfunction "~{SHDN}_4") (pintype "input"))
      (node (ref "U1") (pin "5") (pinfunction "VIN_5") (pintype "power_in"))
    )
    (net (code "62") (name "GND") (class "Default")
      (node (ref "C1") (pin "2") (pinfunction "2_2") (pintype "passive"))
      (node (ref "C10") (pin "2") (pinfunction "2_2") (pintype "passive"))
      (node (ref "C11") (pin "2") (pinfunction "2_2") (pintype "passive"))
      (node (ref "C12") (pin "1") (pinfunction "1_1") (pintype "passive"))
      (node (ref "C13") (pin "1") (pinfunction "1_1") (pintype "passive"))
      (node (ref "C14") (pin "1") (pinfunction "1_1") (pintype "passive"))
      (node (ref "C15") (pin "1") (pinfunction "1_1") (pintype "passive"))
      (node (ref "C17") (pin "-") (pinfunction "-_-") (pintype "passive"))
      (node (ref "C18") (pin "-") (pinfunction "-_-") (pintype "passive"))
      (node (ref "C19") (pin "-") (pinfunction "-_-") (pintype "passive"))
      (node (ref "C2") (pin "-") (pinfunction "-_-") (pintype "passive"))
      (node (ref "C20") (pin "-") (pinfunction "-_-") (pintype "passive"))
      (node (ref "C3") (pin "2") (pinfunction "2_2") (pintype "passive"))
      (node (ref "C5") (pin "1") (pinfunction "1_1") (pintype "passive"))
      (node (ref "C6") (pin "1") (pinfunction "1_1") (pintype "passive"))
      (node (ref "C7") (pin "1") (pinfunction "1_1") (pintype "passive"))
      (node (ref "C8") (pin "2") (pinfunction "2_2") (pintype "passive"))
      (node (ref "C9") (pin "1") (pinfunction "1_1") (pintype "passive"))
      (node (ref "D1") (pin "A") (pinfunction "A_A") (pintype "passive"))
      (node (ref "D2") (pin "A") (pinfunction "A_A") (pintype "passive"))
      (node (ref "J1") (pin "2") (pinfunction "2_2") (pintype "passive"))
      (node (ref "J11") (pin "2") (pinfunction "2_2") (pintype "passive"))
      (node (ref "J12") (pin "2") (pinfunction "2_2") (pintype "passive"))
      (node (ref "J2") (pin "6") (pinfunction "GND_6") (pintype "power_in"))
      (node (ref "J2") (pin "C1") (pinfunction "SHEILD_C1") (pintype "bidirectional"))
      (node (ref "J2") (pin "C2") (pinfunction "SHIELD_C2") (pintype "bidirectional"))
      (node (ref "J2") (pin "C3") (pinfunction "SHIELD_C3") (pintype "bidirectional"))
      (node (ref "J2") (pin "C4") (pinfunction "SHIELD_C4") (pintype "bidirectional"))
      (node (ref "J2") (pin "CD1") (pinfunction "CD1_CD1") (pintype "bidirectional"))
      (node (ref "J3") (pin "GND") (pinfunction "GND_GND") (pintype "bidirectional"))
      (node (ref "J3") (pin "GND1") (pinfunction "GND_GND1") (pintype "bidirectional"))
      (node (ref "J3") (pin "GND2") (pinfunction "GND_GND2") (pintype "bidirectional"))
      (node (ref "J3") (pin "GND3") (pinfunction "GND_GND3") (pintype "bidirectional"))
      (node (ref "J3") (pin "GND4") (pinfunction "GND_GND4") (pintype "bidirectional"))
      (node (ref "J3") (pin "GND5") (pinfunction "GND_GND5") (pintype "bidirectional"))
      (node (ref "J3") (pin "GND6") (pinfunction "GND_GND6") (pintype "bidirectional"))
      (node (ref "J3") (pin "GND7") (pinfunction "GND_GND7") (pintype "bidirectional"))
      (node (ref "J3") (pin "GND8") (pinfunction "GND_GND8") (pintype "bidirectional"))
      (node (ref "J5") (pin "3") (pinfunction "3_3") (pintype "power_in"))
      (node (ref "J5") (pin "4") (pinfunction "4_4") (pintype "power_in"))
      (node (ref "J6") (pin "4") (pinfunction "S_4") (pintype "passive"))
      (node (ref "J6") (pin "5") (pinfunction "S_5") (pintype "passive"))
      (node (ref "J6") (pin "6") (pinfunction "S_6") (pintype "passive"))
      (node (ref "J8") (pin "1") (pinfunction "1_1") (pintype "passive"))
      (node (ref "JP10") (pin "3") (pinfunction "3_3") (pintype "passive"))
      (node (ref "JP3") (pin "2") (pinfunction "2_2") (pintype "passive"))
      (node (ref "JP5") (pin "1") (pinfunction "1_1") (pintype "passive"))
      (node (ref "JP7") (pin "3") (pinfunction "3_3") (pintype "passive"))
      (node (ref "JP8") (pin "3") (pinfunction "3_3") (pintype "passive"))
      (node (ref "JP9") (pin "3") (pinfunction "3_3") (pintype "passive"))
      (node (ref "LED1") (pin "C") (pinfunction "C_C") (pintype "passive"))
      (node (ref "P1") (pin "GNDMOT") (pinfunction "GNDMOT_GNDMOT") (pintype "power_in"))
      (node (ref "P1") (pin "GNDVDD") (pinfunction "GNDVDD_GNDVDD") (pintype "power_in"))
      (node (ref "P2") (pin "GNDMOT") (pinfunction "GNDMOT_GNDMOT") (pintype "power_in"))
      (node (ref "P2") (pin "GNDVDD") (pinfunction "GNDVDD_GNDVDD") (pintype "power_in"))
      (node (ref "P3") (pin "GNDMOT") (pinfunction "GNDMOT_GNDMOT") (pintype "power_in"))
      (node (ref "P3") (pin "GNDVDD") (pinfunction "GNDVDD_GNDVDD") (pintype "power_in"))
      (node (ref "P4") (pin "GNDMOT") (pinfunction "GNDMOT_GNDMOT") (pintype "power_in"))
      (node (ref "P4") (pin "GNDVDD") (pinfunction "GNDVDD_GNDVDD") (pintype "power_in"))
      (node (ref "Q1") (pin "2") (pinfunction "S_2") (pintype "passive"))
      (node (ref "Q2") (pin "1") (pinfunction "S1_1") (pintype "passive"))
      (node (ref "Q2") (pin "2") (pinfunction "S2_2") (pintype "passive"))
      (node (ref "Q2") (pin "3") (pinfunction "S3_3") (pintype "passive"))
      (node (ref "Q3") (pin "1") (pinfunction "S1_1") (pintype "passive"))
      (node (ref "Q3") (pin "2") (pinfunction "S2_2") (pintype "passive"))
      (node (ref "Q3") (pin "3") (pinfunction "S3_3") (pintype "passive"))
      (node (ref "Q5") (pin "3") (pinfunction "C_3") (pintype "passive"))
      (node (ref "R10") (pin "2") (pinfunction "2_2") (pintype "passive"))
      (node (ref "R2") (pin "2") (pinfunction "2_2") (pintype "passive"))
      (node (ref "R5") (pin "2") (pinfunction "2_2") (pintype "passive"))
      (node (ref "R8") (pin "2") (pinfunction "2_2") (pintype "passive"))
      (node (ref "S1") (pin "1") (pinfunction "1_1") (pintype "passive"))
      (node (ref "S1") (pin "2") (pinfunction "2_2") (pintype "passive"))
      (node (ref "SCREW1") (pin "GND") (pinfunction "P$1_GND") (pintype "bidirectional"))
      (node (ref "SCREW2") (pin "GND") (pinfunction "P$1_GND") (pintype "bidirectional"))
      (node (ref "SCREW3") (pin "GND") (pinfunction "P$1_GND") (pintype "bidirectional"))
      (node (ref "SCREW4") (pin "GND") (pinfunction "P$1_GND") (pintype "bidirectional"))
      (node (ref "U1") (pin "2") (pinfunction "GND_2") (pintype "power_in"))
      (node (ref "U2") (pin "2") (pinfunction "GND_2") (pintype "power_in"))
      (node (ref "U3") (pin "3") (pinfunction "GND_3") (pintype "power_in"))
      (node (ref "U4") (pin "7") (pinfunction "GND_7") (pintype "power_in"))
      (node (ref "U5") (pin "22") (pinfunction "GND_22") (pintype "power_in"))
      (node (ref "U5") (pin "53") (pinfunction "GND_53") (pintype "power_in"))
      (node (ref "U5") (pin "6") (pinfunction "UGND_6") (pintype "power_in"))
      (node (ref "U5") (pin "63") (pinfunction "AGND_63") (pintype "power_in"))
    )
    (net (code "63") (name "Net-(F1-PadP$2)") (class "Default")
      (node (ref "F1") (pin "P$2") (pinfunction "P$2_P$2") (pintype "passive"))
      (node (ref "J4") (pin "2") (pinfunction "2_2") (pintype "passive"))
    )
    (net (code "64") (name "Net-(J6A-S)") (class "Default")
      (node (ref "F2") (pin "P$1") (pinfunction "P$1_P$1") (pintype "passive"))
      (node (ref "F2") (pin "P$2") (pinfunction "P$2_P$2") (pintype "passive"))
      (node (ref "J5") (pin "1") (pinfunction "1_1") (pintype "power_in"))
      (node (ref "J5") (pin "2") (pinfunction "2_2") (pintype "power_in"))
      (node (ref "J6") (pin "1") (pinfunction "S_1") (pintype "passive"))
      (node (ref "J6") (pin "2") (pinfunction "S_2") (pintype "passive"))
      (node (ref "J6") (pin "3") (pinfunction "S_3") (pintype "passive"))
    )
    (net (code "65") (name "Net-(JP6-Pad2)") (class "Default")
      (node (ref "JP6") (pin "2") (pinfunction "2_2") (pintype "passive"))
      (node (ref "JP7") (pin "2") (pinfunction "2_2") (pintype "passive"))
    )
    (net (code "66") (name "Net-(JP10-Pad2)") (class "Default")
      (node (ref "JP10") (pin "2") (pinfunction "2_2") (pintype "passive"))
      (node (ref "JP4") (pin "2") (pinfunction "2_2") (pintype "passive"))
      (node (ref "JP8") (pin "2") (pinfunction "2_2") (pintype "passive"))
      (node (ref "JP9") (pin "2") (pinfunction "2_2") (pintype "passive"))
    )
    (net (code "67") (name "Net-(LED1-PadA)") (class "Default")
      (node (ref "LED1") (pin "A") (pinfunction "A_A") (pintype "passive"))
      (node (ref "R1") (pin "1") (pinfunction "1_1") (pintype "passive"))
    )
    (net (code "68") (name "Net-(P1-MOT-1A)") (class "Default")
      (node (ref "JP11") (pin "3") (pinfunction "3_3") (pintype "passive"))
      (node (ref "P1") (pin "1A") (pinfunction "MOT-1A_1A") (pintype "power_in"))
    )
    (net (code "69") (name "Net-(P1-MOT-1B)") (class "Default")
      (node (ref "JP11") (pin "4") (pinfunction "4_4") (pintype "passive"))
      (node (ref "P1") (pin "1B") (pinfunction "MOT-1B_1B") (pintype "power_in"))
    )
    (net (code "70") (name "Net-(P1-MOT-2A)") (class "Default")
      (node (ref "JP11") (pin "2") (pinfunction "2_2") (pintype "passive"))
      (node (ref "P1") (pin "2A") (pinfunction "MOT-2A_2A") (pintype "power_in"))
    )
    (net (code "71") (name "Net-(P1-MOT-2B)") (class "Default")
      (node (ref "JP11") (pin "1") (pinfunction "1_1") (pintype "passive"))
      (node (ref "P1") (pin "2B") (pinfunction "MOT-2B_2B") (pintype "power_in"))
    )
    (net (code "72") (name "Net-(P1-PadMS1)") (class "Default")
      (node (ref "P1") (pin "MS1") (pinfunction "MS1_MS1") (pintype "input"))
      (node (ref "SJ12") (pin "1") (pinfunction "1_1") (pintype "passive"))
    )
    (net (code "73") (name "Net-(P1-PadMS2)") (class "Default")
      (node (ref "P1") (pin "MS2") (pinfunction "MS2_MS2") (pintype "input"))
      (node (ref "SJ7") (pin "1") (pinfunction "1_1") (pintype "passive"))
    )
    (net (code "74") (name "Net-(P1-PadMS3)") (class "Default")
      (node (ref "P1") (pin "MS3") (pinfunction "MS3_MS3") (pintype "input"))
      (node (ref "SJ2") (pin "1") (pinfunction "1_1") (pintype "passive"))
    )
    (net (code "75") (name "Net-(P1-~{RESET})") (class "Default")
      (node (ref "P1") (pin "!RST") (pinfunction "~{RESET}_!RST") (pintype "input"))
      (node (ref "P1") (pin "!SLP") (pinfunction "~{SLEEP}_!SLP") (pintype "input"))
    )
    (net (code "76") (name "Net-(P2-MOT-1A)") (class "Default")
      (node (ref "JP12") (pin "3") (pinfunction "3_3") (pintype "passive"))
      (node (ref "P2") (pin "1A") (pinfunction "MOT-1A_1A") (pintype "power_in"))
    )
    (net (code "77") (name "Net-(P2-MOT-1B)") (class "Default")
      (node (ref "JP12") (pin "4") (pinfunction "4_4") (pintype "passive"))
      (node (ref "P2") (pin "1B") (pinfunction "MOT-1B_1B") (pintype "power_in"))
    )
    (net (code "78") (name "Net-(P2-MOT-2A)") (class "Default")
      (node (ref "JP12") (pin "2") (pinfunction "2_2") (pintype "passive"))
      (node (ref "P2") (pin "2A") (pinfunction "MOT-2A_2A") (pintype "power_in"))
    )
    (net (code "79") (name "Net-(P2-MOT-2B)") (class "Default")
      (node (ref "JP12") (pin "1") (pinfunction "1_1") (pintype "passive"))
      (node (ref "P2") (pin "2B") (pinfunction "MOT-2B_2B") (pintype "power_in"))
    )
    (net (code "80") (name "Net-(P2-PadMS1)") (class "Default")
      (node (ref "P2") (pin "MS1") (pinfunction "MS1_MS1") (pintype "input"))
      (node (ref "SJ13") (pin "1") (pinfunction "1_1") (pintype "passive"))
    )
    (net (code "81") (name "Net-(P2-PadMS2)") (class "Default")
      (node (ref "P2") (pin "MS2") (pinfunction "MS2_MS2") (pintype "input"))
      (node (ref "SJ8") (pin "1") (pinfunction "1_1") (pintype "passive"))
    )
    (net (code "82") (name "Net-(P2-PadMS3)") (class "Default")
      (node (ref "P2") (pin "MS3") (pinfunction "MS3_MS3") (pintype "input"))
      (node (ref "SJ3") (pin "1") (pinfunction "1_1") (pintype "passive"))
    )
    (net (code "83") (name "Net-(P2-~{RESET})") (class "Default")
      (node (ref "P2") (pin "!RST") (pinfunction "~{RESET}_!RST") (pintype "input"))
      (node (ref "P2") (pin "!SLP") (pinfunction "~{SLEEP}_!SLP") (pintype "input"))
    )
    (net (code "84") (name "Net-(P3-MOT-1A)") (class "Default")
      (node (ref "JP15") (pin "3") (pinfunction "3_3") (pintype "passive"))
      (node (ref "P3") (pin "1A") (pinfunction "MOT-1A_1A") (pintype "power_in"))
    )
    (net (code "85") (name "Net-(P3-MOT-1B)") (class "Default")
      (node (ref "JP15") (pin "4") (pinfunction "4_4") (pintype "passive"))
      (node (ref "P3") (pin "1B") (pinfunction "MOT-1B_1B") (pintype "power_in"))
    )
    (net (code "86") (name "Net-(P3-MOT-2A)") (class "Default")
      (node (ref "JP15") (pin "2") (pinfunction "2_2") (pintype "passive"))
      (node (ref "P3") (pin "2A") (pinfunction "MOT-2A_2A") (pintype "power_in"))
    )
    (net (code "87") (name "Net-(P3-MOT-2B)") (class "Default")
      (node (ref "JP15") (pin "1") (pinfunction "1_1") (pintype "passive"))
      (node (ref "P3") (pin "2B") (pinfunction "MOT-2B_2B") (pintype "power_in"))
    )
    (net (code "88") (name "Net-(P3-PadMS1)") (class "Default")
      (node (ref "P3") (pin "MS1") (pinfunction "MS1_MS1") (pintype "input"))
      (node (ref "SJ14") (pin "1") (pinfunction "1_1") (pintype "passive"))
    )
    (net (code "89") (name "Net-(P3-PadMS2)") (class "Default")
      (node (ref "P3") (pin "MS2") (pinfunction "MS2_MS2") (pintype "input"))
      (node (ref "SJ9") (pin "1") (pinfunction "1_1") (pintype "passive"))
    )
    (net (code "90") (name "Net-(P3-PadMS3)") (class "Default")
      (node (ref "P3") (pin "MS3") (pinfunction "MS3_MS3") (pintype "input"))
      (node (ref "SJ4") (pin "1") (pinfunction "1_1") (pintype "passive"))
    )
    (net (code "91") (name "Net-(P3-~{RESET})") (class "Default")
      (node (ref "P3") (pin "!RST") (pinfunction "~{RESET}_!RST") (pintype "input"))
      (node (ref "P3") (pin "!SLP") (pinfunction "~{SLEEP}_!SLP") (pintype "input"))
    )
    (net (code "92") (name "Net-(P4-MOT-1A)") (class "Default")
      (node (ref "JP13") (pin "3") (pinfunction "3_3") (pintype "passive"))
      (node (ref "P4") (pin "1A") (pinfunction "MOT-1A_1A") (pintype "power_in"))
    )
    (net (code "93") (name "Net-(P4-MOT-1B)") (class "Default")
      (node (ref "JP13") (pin "4") (pinfunction "4_4") (pintype "passive"))
      (node (ref "P4") (pin "1B") (pinfunction "MOT-1B_1B") (pintype "power_in"))
    )
    (net (code "94") (name "Net-(P4-MOT-2A)") (class "Default")
      (node (ref "JP13") (pin "2") (pinfunction "2_2") (pintype "passive"))
      (node (ref "P4") (pin "2A") (pinfunction "MOT-2A_2A") (pintype "power_in"))
    )
    (net (code "95") (name "Net-(P4-MOT-2B)") (class "Default")
      (node (ref "JP13") (pin "1") (pinfunction "1_1") (pintype "passive"))
      (node (ref "P4") (pin "2B") (pinfunction "MOT-2B_2B") (pintype "power_in"))
    )
    (net (code "96") (name "Net-(P4-PadMS1)") (class "Default")
      (node (ref "P4") (pin "MS1") (pinfunction "MS1_MS1") (pintype "input"))
      (node (ref "SJ15") (pin "1") (pinfunction "1_1") (pintype "passive"))
    )
    (net (code "97") (name "Net-(P4-PadMS2)") (class "Default")
      (node (ref "P4") (pin "MS2") (pinfunction "MS2_MS2") (pintype "input"))
      (node (ref "SJ10") (pin "1") (pinfunction "1_1") (pintype "passive"))
    )
    (net (code "98") (name "Net-(P4-PadMS3)") (class "Default")
      (node (ref "P4") (pin "MS3") (pinfunction "MS3_MS3") (pintype "input"))
      (node (ref "SJ5") (pin "1") (pinfunction "1_1") (pintype "passive"))
    )
    (net (code "99") (name "Net-(P4-~{RESET})") (class "Default")
      (node (ref "P4") (pin "!RST") (pinfunction "~{RESET}_!RST") (pintype "input"))
      (node (ref "P4") (pin "!SLP") (pinfunction "~{SLEEP}_!SLP") (pintype "input"))
    )
    (net (code "100") (name "Net-(Q1-D)") (class "Default")
      (node (ref "D2") (pin "C") (pinfunction "C_C") (pintype "passive"))
      (node (ref "F1") (pin "P$1") (pinfunction "P$1_P$1") (pintype "passive"))
      (node (ref "Q1") (pin "3") (pinfunction "D_3") (pintype "passive"))
    )
    (net (code "101") (name "Net-(Q1-G)") (class "Default")
      (node (ref "Q1") (pin "1") (pinfunction "G_1") (pintype "passive"))
      (node (ref "R3") (pin "2") (pinfunction "2_2") (pintype "passive"))
    )
    (net (code "102") (name "Net-(Q2-D)") (class "Default")
      (node (ref "J7") (pin "1") (pinfunction "1_1") (pintype "power_in"))
      (node (ref "J7") (pin "2") (pinfunction "2_2") (pintype "power_in"))
      (node (ref "Q2") (pin "5-8") (pinfunction "D_5-8") (pintype "passive"))
    )
    (net (code "103") (name "Net-(Q2-G)") (class "Default")
      (node (ref "Q2") (pin "4") (pinfunction "G_4") (pintype "passive"))
      (node (ref "R9") (pin "2") (pinfunction "2_2") (pintype "passive"))
    )
    (net (code "104") (name "Net-(Q3-D)") (class "Default")
      (node (ref "J9") (pin "1") (pinfunction "1_1") (pintype "power_in"))
      (node (ref "J9") (pin "2") (pinfunction "2_2") (pintype "power_in"))
      (node (ref "Q3") (pin "5-8") (pinfunction "D_5-8") (pintype "passive"))
    )
    (net (code "105") (name "Net-(Q3-G)") (class "Default")
      (node (ref "Q3") (pin "4") (pinfunction "G_4") (pintype "passive"))
      (node (ref "R11") (pin "2") (pinfunction "2_2") (pintype "passive"))
    )
    (net (code "106") (name "Net-(Q5-B)") (class "Default")
      (node (ref "JP7") (pin "1") (pinfunction "1_1") (pintype "passive"))
      (node (ref "Q5") (pin "1") (pinfunction "B_1") (pintype "passive"))
    )
    (net (code "107") (name "Net-(U1-CB)") (class "Default")
      (node (ref "C4") (pin "2") (pinfunction "2_2") (pintype "passive"))
      (node (ref "U1") (pin "1") (pinfunction "CB_1") (pintype "passive"))
    )
    (net (code "108") (name "Net-(U1-FB)") (class "Default")
      (node (ref "R4") (pin "2") (pinfunction "2_2") (pintype "passive"))
      (node (ref "R5") (pin "1") (pinfunction "1_1") (pintype "passive"))
      (node (ref "U1") (pin "3") (pinfunction "FB_3") (pintype "passive"))
    )
    (net (code "109") (name "Net-(U1-SW)") (class "Default")
      (node (ref "C4") (pin "1") (pinfunction "1_1") (pintype "passive"))
      (node (ref "D1") (pin "C") (pinfunction "C_C") (pintype "passive"))
      (node (ref "L1") (pin "1") (pinfunction "1_1") (pintype "passive"))
      (node (ref "U1") (pin "6") (pinfunction "SW_6") (pintype "passive"))
    )
    (net (code "110") (name "Net-(U5-D+)") (class "Default")
      (node (ref "R7") (pin "2") (pinfunction "2_2") (pintype "passive"))
      (node (ref "U5") (pin "5") (pinfunction "D+_5") (pintype "bidirectional"))
    )
    (net (code "111") (name "Net-(U5-D-)") (class "Default")
      (node (ref "R6") (pin "2") (pinfunction "2_2") (pintype "passive"))
      (node (ref "U5") (pin "4") (pinfunction "D-_4") (pintype "bidirectional"))
    )
    (net (code "112") (name "Net-(U5-UCAP)") (class "Default")
      (node (ref "C9") (pin "2") (pinfunction "2_2") (pintype "passive"))
      (node (ref "U5") (pin "7") (pinfunction "UCAP_7") (pintype "power_in"))
    )
    (net (code "113") (name "unconnected-(J2-DAT1-Pad8)") (class "Default")
      (node (ref "J2") (pin "8") (pinfunction "DAT1_8") (pintype "bidirectional"))
    )
    (net (code "114") (name "unconnected-(J2-DAT2-Pad1)") (class "Default")
      (node (ref "J2") (pin "1") (pinfunction "DAT2_1") (pintype "bidirectional"))
    )
    (net (code "115") (name "unconnected-(U2-IO3-Pad4)") (class "Default")
      (node (ref "U2") (pin "4") (pinfunction "IO3_4") (pintype "bidirectional"))
    )
    (net (code "116") (name "unconnected-(U2-IO4-Pad6)") (class "Default")
      (node (ref "U2") (pin "6") (pinfunction "IO4_6") (pintype "bidirectional"))
    )
  )
)
